# mackb_breakout.net
KiCad netlist of a schematic drawn in EAGLE
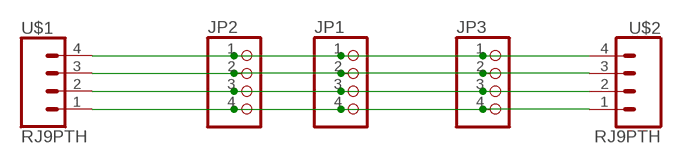
[diagram p0: schematic, sheet 1]

(export (version "E")
  (design (tool "Eeschema 10.0.6"))
  (components
    (comp (ref "JP1")
      (value "PINHD-1X4")
      (footprint "eagle-import:1X04")
      (libsource (lib "eagle-import") (part "PINHD-1X4"))
    )
    (comp (ref "JP2")
      (value "PINHD-1X4")
      (footprint "eagle-import:1X04")
      (libsource (lib "eagle-import") (part "PINHD-1X4"))
    )
    (comp (ref "JP3")
      (value "PINHD-1X4")
      (footprint "eagle-import:1X04")
      (libsource (lib "eagle-import") (part "PINHD-1X4"))
    )
    (comp (ref "U$1")
      (value "RJ9PTH")
      (footprint "eagle-import:RJ9")
      (libsource (lib "eagle-import") (part "RJ9PTH"))
    )
    (comp (ref "U$2")
      (value "RJ9PTH")
      (footprint "eagle-import:RJ9")
      (libsource (lib "eagle-import") (part "RJ9PTH"))
    )
  )
  (nets
    (net (code "1") (name "Net-(JP1-Pad1)") (class "Default")
      (node (ref "JP1") (pin "1") (pinfunction "1_1") (pintype "passive"))
      (node (ref "JP2") (pin "1") (pinfunction "1_1") (pintype "passive"))
      (node (ref "JP3") (pin "1") (pinfunction "1_1") (pintype "passive"))
      (node (ref "U$1") (pin "4") (pinfunction "4_4") (pintype "passive"))
      (node (ref "U$2") (pin "4") (pinfunction "4_4") (pintype "passive"))
    )
    (net (code "2") (name "Net-(JP1-Pad2)") (class "Default")
      (node (ref "JP1") (pin "2") (pinfunction "2_2") (pintype "passive"))
      (node (ref "JP2") (pin "2") (pinfunction "2_2") (pintype "passive"))
      (node (ref "JP3") (pin "2") (pinfunction "2_2") (pintype "passive"))
      (node (ref "U$1") (pin "3") (pinfunction "3_3") (pintype "passive"))
      (node (ref "U$2") (pin "3") (pinfunction "3_3") (pintype "passive"))
    )
    (net (code "3") (name "Net-(JP1-Pad3)") (class "Default")
      (node (ref "JP1") (pin "3") (pinfunction "3_3") (pintype "passive"))
      (node (ref "JP2") (pin "3") (pinfunction "3_3") (pintype "passive"))
      (node (ref "JP3") (pin "3") (pinfunction "3_3") (pintype "passive"))
      (node (ref "U$1") (pin "2") (pinfunction "2_2") (pintype "passive"))
      (node (ref "U$2") (pin "2") (pinfunction "2_2") (pintype "passive"))
    )
    (net (code "4") (name "Net-(JP1-Pad4)") (class "Default")
      (node (ref "JP1") (pin "4") (pinfunction "4_4") (pintype "passive"))
      (node (ref "JP2") (pin "4") (pinfunction "4_4") (pintype "passive"))
      (node (ref "JP3") (pin "4") (pinfunction "4_4") (pintype "passive"))
      (node (ref "U$1") (pin "1") (pinfunction "1_1") (pintype "passive"))
      (node (ref "U$2") (pin "1") (pinfunction "1_1") (pintype "passive"))
    )
  )
)
